# SensorBoard.net
KiCad netlist of a schematic drawn in EAGLE
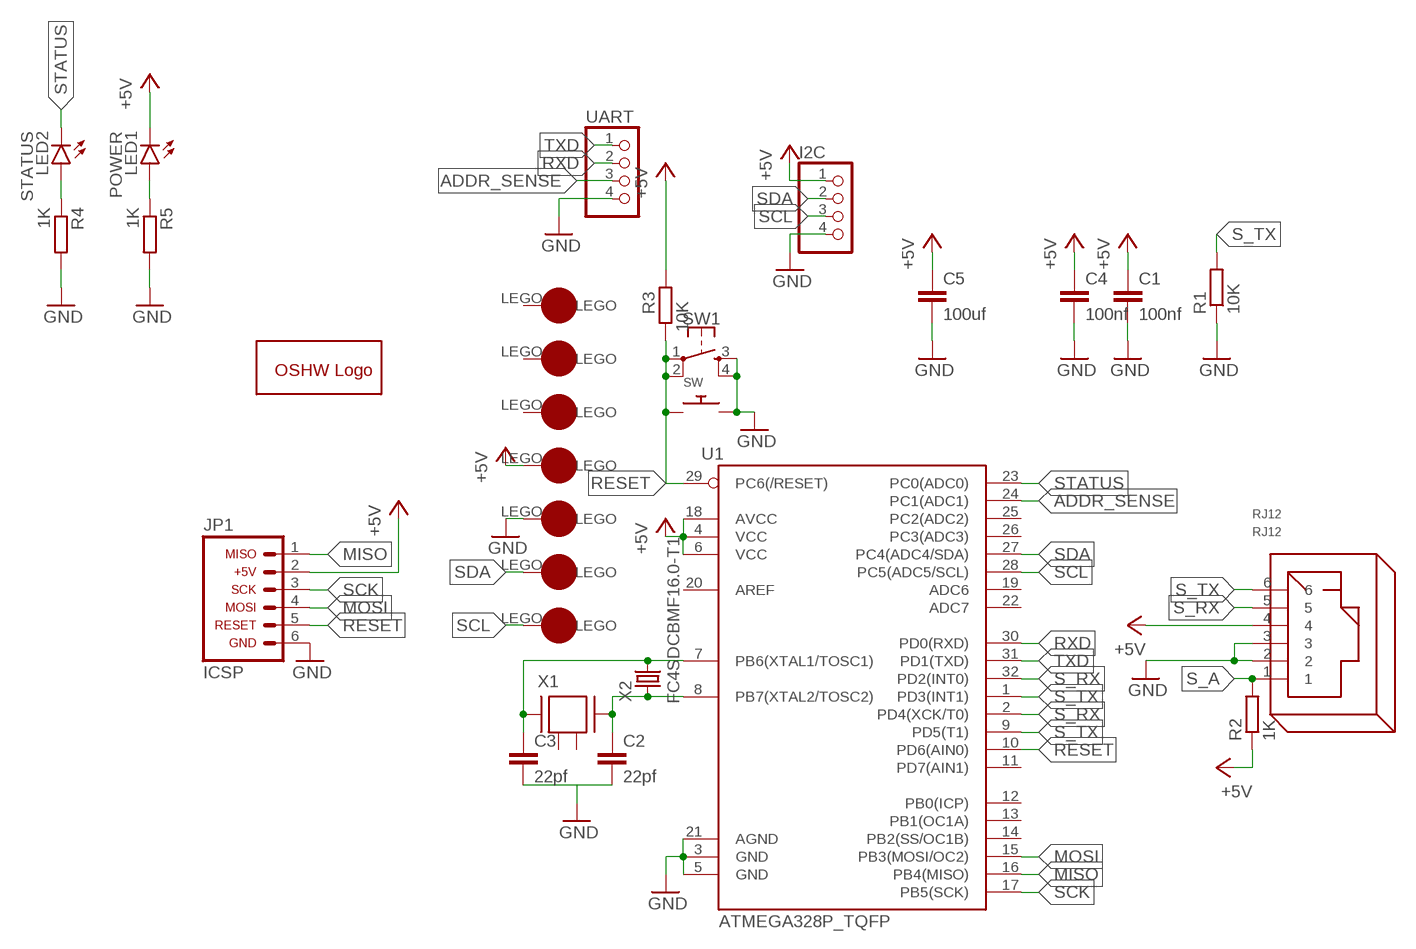
[diagram p0: schematic, sheet 1]

(export (version "E")
  (design (tool "Eeschema 10.0.6"))
  (components
    (comp (ref "C1")
      (value "100nf")
      (footprint "eagle-import:C1206")
      (libsource (lib "eagle-import") (part "C-EUC1206"))
    )
    (comp (ref "C2")
      (value "22pf")
      (footprint "eagle-import:C1206")
      (libsource (lib "eagle-import") (part "C-EUC1206"))
    )
    (comp (ref "C3")
      (value "22pf")
      (footprint "eagle-import:C1206")
      (libsource (lib "eagle-import") (part "C-EUC1206"))
    )
    (comp (ref "C4")
      (value "100nf")
      (footprint "eagle-import:C1206")
      (libsource (lib "eagle-import") (part "C-EUC1206"))
    )
    (comp (ref "C5")
      (value "100uf")
      (footprint "eagle-import:C1206")
      (libsource (lib "eagle-import") (part "C-EUC1206"))
    )
    (comp (ref "I2C")
      (value "PINHD-1X4")
      (footprint "eagle-import:1X04")
      (libsource (lib "eagle-import") (part "PINHD-1X4"))
    )
    (comp (ref "JP1")
      (value "ICSP_HEADER")
      (footprint "eagle-import:ICSP_HEADER")
      (libsource (lib "eagle-import") (part "ICSP_HEADER"))
    )
    (comp (ref "LED1")
      (value "POWER")
      (footprint "eagle-import:1206")
      (libsource (lib "eagle-import") (part "LEDSMT1206"))
    )
    (comp (ref "LED2")
      (value "STATUS")
      (footprint "eagle-import:1206")
      (libsource (lib "eagle-import") (part "LEDSMT1206"))
    )
    (comp (ref "R1")
      (value "10K")
      (footprint "eagle-import:M1206")
      (libsource (lib "eagle-import") (part "R-EU_M1206"))
    )
    (comp (ref "R2")
      (value "1K")
      (footprint "eagle-import:M1206")
      (libsource (lib "eagle-import") (part "R-EU_M1206"))
    )
    (comp (ref "R3")
      (value "10K")
      (footprint "eagle-import:M1206")
      (libsource (lib "eagle-import") (part "R-EU_M1206"))
    )
    (comp (ref "R4")
      (value "1K")
      (footprint "eagle-import:M1206")
      (libsource (lib "eagle-import") (part "R-EU_M1206"))
    )
    (comp (ref "R5")
      (value "1K")
      (footprint "eagle-import:M1206")
      (libsource (lib "eagle-import") (part "R-EU_M1206"))
    )
    (comp (ref "RJ12")
      (value "RJ12")
      (footprint "eagle-import:RJ12")
      (libsource (lib "eagle-import") (part "RJ12"))
    )
    (comp (ref "SW")
      (value "SWITCH_PUSHBUTTONC&K_KSS")
      (footprint "eagle-import:BTN_CK_KSS")
      (libsource (lib "eagle-import") (part "SWITCH_PUSHBUTTONC&K_KSS"))
    )
    (comp (ref "SW1")
      (value "MOMENTARY-SWITCH-SPST-2-SMD-5.2MM")
      (footprint "eagle-import:TACTILE_SWITCH_SMD_5.2MM")
      (libsource (lib "eagle-import") (part "MOMENTARY-SWITCH-SPST-2-SMD-5.2MM"))
    )
    (comp (ref "U$1")
      (value "LEGO-1X1")
      (footprint "eagle-import:LEGO-1X1")
      (libsource (lib "eagle-import") (part "LEGO-1X1"))
    )
    (comp (ref "U$2")
      (value "OPENSOURCE")
      (footprint "eagle-import:OSHW_5MM")
      (libsource (lib "eagle-import") (part "OPENSOURCE"))
    )
    (comp (ref "U$3")
      (value "LEGO-1X1")
      (footprint "eagle-import:LEGO-1X1")
      (libsource (lib "eagle-import") (part "LEGO-1X1"))
    )
    (comp (ref "U$4")
      (value "LEGO-1X1")
      (footprint "eagle-import:LEGO-1X1")
      (libsource (lib "eagle-import") (part "LEGO-1X1"))
    )
    (comp (ref "U$5")
      (value "LEGO-1X1")
      (footprint "eagle-import:LEGO-1X1")
      (libsource (lib "eagle-import") (part "LEGO-1X1"))
    )
    (comp (ref "U$6")
      (value "LEGO-1X1")
      (footprint "eagle-import:LEGO-1X1")
      (libsource (lib "eagle-import") (part "LEGO-1X1"))
    )
    (comp (ref "U$7")
      (value "LEGO-1X1")
      (footprint "eagle-import:LEGO-1X1")
      (libsource (lib "eagle-import") (part "LEGO-1X1"))
    )
    (comp (ref "U$9")
      (value "LEGO-1X1")
      (footprint "eagle-import:LEGO-1X1")
      (libsource (lib "eagle-import") (part "LEGO-1X1"))
    )
    (comp (ref "U1")
      (value "ATMEGA328P_TQFP")
      (footprint "eagle-import:TQFP32-08")
      (libsource (lib "eagle-import") (part "ATMEGA328P_TQFP"))
    )
    (comp (ref "UART")
      (value "PINHD-1X4")
      (footprint "eagle-import:1X04")
      (libsource (lib "eagle-import") (part "PINHD-1X4"))
    )
    (comp (ref "X1")
      (value "7B-16.000MAAJ-T")
      (footprint "eagle-import:7B-16.000MAAJ-T")
      (fields
        (field (name "DIGIKEY_PART_NUMBER") "887-1104-2-ND")
        (field (name "MANUFACTURER") "TXC CORPORATION")
      )
      (libsource (lib "eagle-import") (part "7B-16.000MAAJ-T"))
    )
    (comp (ref "X2")
      (value "FC4SDCBMF16.0-T1")
      (footprint "eagle-import:FC4SDCBMF16.0-T1")
      (fields
        (field (name "DIGIKEY_PART_NUMBER") "631-1017-2-ND")
        (field (name "MANUFACTURER") "Fox Electronics")
        (field (name "CREATED_BY") "PCBLayout.com")
      )
      (libsource (lib "eagle-import") (part "FC4SDCBMF16.0-T1"))
    )
  )
  (nets
    (net (code "1") (name "+5V") (class "Default")
      (node (ref "C1") (pin "1") (pinfunction "1_1") (pintype "passive"))
      (node (ref "C4") (pin "1") (pinfunction "1_1") (pintype "passive"))
      (node (ref "C5") (pin "1") (pinfunction "1_1") (pintype "passive"))
      (node (ref "I2C") (pin "1") (pinfunction "1_1") (pintype "passive"))
      (node (ref "JP1") (pin "2") (pinfunction "2_2") (pintype "passive"))
      (node (ref "LED1") (pin "C") (pinfunction "C_C") (pintype "passive"))
      (node (ref "R2") (pin "1") (pinfunction "1_1") (pintype "passive"))
      (node (ref "R3") (pin "2") (pinfunction "2_2") (pintype "passive"))
      (node (ref "RJ12") (pin "4") (pinfunction "4_4") (pintype "bidirectional"))
      (node (ref "U$5") (pin "LEGO") (pinfunction "LEGO_LEGO") (pintype "bidirectional"))
      (node (ref "U1") (pin "18") (pinfunction "AVCC_18") (pintype "bidirectional"))
      (node (ref "U1") (pin "4") (pinfunction "VCC_4") (pintype "bidirectional"))
      (node (ref "U1") (pin "6") (pinfunction "VCC_6") (pintype "bidirectional"))
    )
    (net (code "2") (name "ADDR_SENSE") (class "Default")
      (node (ref "U1") (pin "24") (pinfunction "PC1(ADC1)_24") (pintype "bidirectional"))
      (node (ref "UART") (pin "3") (pinfunction "3_3") (pintype "passive"))
    )
    (net (code "3") (name "GND") (class "Default")
      (node (ref "C1") (pin "2") (pinfunction "2_2") (pintype "passive"))
      (node (ref "C2") (pin "2") (pinfunction "2_2") (pintype "passive"))
      (node (ref "C3") (pin "2") (pinfunction "2_2") (pintype "passive"))
      (node (ref "C4") (pin "2") (pinfunction "2_2") (pintype "passive"))
      (node (ref "C5") (pin "2") (pinfunction "2_2") (pintype "passive"))
      (node (ref "I2C") (pin "4") (pinfunction "4_4") (pintype "passive"))
      (node (ref "JP1") (pin "6") (pinfunction "6_6") (pintype "passive"))
      (node (ref "R1") (pin "1") (pinfunction "1_1") (pintype "passive"))
      (node (ref "R4") (pin "2") (pinfunction "2_2") (pintype "passive"))
      (node (ref "R5") (pin "2") (pinfunction "2_2") (pintype "passive"))
      (node (ref "RJ12") (pin "2") (pinfunction "2_2") (pintype "bidirectional"))
      (node (ref "RJ12") (pin "3") (pinfunction "3_3") (pintype "bidirectional"))
      (node (ref "SW") (pin "P$2") (pinfunction "P$2_P$2") (pintype "passive"))
      (node (ref "SW1") (pin "3") (pinfunction "3_3") (pintype "passive"))
      (node (ref "SW1") (pin "4") (pinfunction "4_4") (pintype "passive"))
      (node (ref "U$4") (pin "LEGO") (pinfunction "LEGO_LEGO") (pintype "bidirectional"))
      (node (ref "U1") (pin "21") (pinfunction "AGND_21") (pintype "bidirectional"))
      (node (ref "U1") (pin "3") (pinfunction "GND_3") (pintype "bidirectional"))
      (node (ref "U1") (pin "5") (pinfunction "GND_5") (pintype "bidirectional"))
      (node (ref "UART") (pin "4") (pinfunction "4_4") (pintype "passive"))
    )
    (net (code "4") (name "MISO") (class "Default")
      (node (ref "JP1") (pin "1") (pinfunction "1_1") (pintype "passive"))
      (node (ref "U1") (pin "16") (pinfunction "PB4(MISO)_16") (pintype "bidirectional"))
    )
    (net (code "5") (name "MOSI") (class "Default")
      (node (ref "JP1") (pin "4") (pinfunction "4_4") (pintype "passive"))
      (node (ref "U1") (pin "15") (pinfunction "PB3(MOSI/OC2)_15") (pintype "bidirectional"))
    )
    (net (code "6") (name "Net-(LED1-PadA)") (class "Default")
      (node (ref "LED1") (pin "A") (pinfunction "A_A") (pintype "passive"))
      (node (ref "R5") (pin "1") (pinfunction "1_1") (pintype "passive"))
    )
    (net (code "7") (name "Net-(LED2-PadA)") (class "Default")
      (node (ref "LED2") (pin "A") (pinfunction "A_A") (pintype "passive"))
      (node (ref "R4") (pin "1") (pinfunction "1_1") (pintype "passive"))
    )
    (net (code "8") (name "Net-(U1-PB6(XTAL1{slash}TOSC1))") (class "Default")
      (node (ref "C3") (pin "1") (pinfunction "1_1") (pintype "passive"))
      (node (ref "U1") (pin "7") (pinfunction "PB6(XTAL1/TOSC1)_7") (pintype "bidirectional"))
      (node (ref "X1") (pin "1") (pinfunction "1_1") (pintype "passive"))
      (node (ref "X2") (pin "2") (pinfunction "2_2") (pintype "passive"))
    )
    (net (code "9") (name "Net-(U1-PB7(XTAL2{slash}TOSC2))") (class "Default")
      (node (ref "C2") (pin "1") (pinfunction "1_1") (pintype "passive"))
      (node (ref "U1") (pin "8") (pinfunction "PB7(XTAL2/TOSC2)_8") (pintype "bidirectional"))
      (node (ref "X1") (pin "3") (pinfunction "3_3") (pintype "passive"))
      (node (ref "X2") (pin "1") (pinfunction "1_1") (pintype "passive"))
    )
    (net (code "10") (name "RESET") (class "Default")
      (node (ref "JP1") (pin "5") (pinfunction "5_5") (pintype "passive"))
      (node (ref "R3") (pin "1") (pinfunction "1_1") (pintype "passive"))
      (node (ref "SW") (pin "P$1") (pinfunction "P$1_P$1") (pintype "passive"))
      (node (ref "SW1") (pin "1") (pinfunction "1_1") (pintype "passive"))
      (node (ref "SW1") (pin "2") (pinfunction "2_2") (pintype "passive"))
      (node (ref "U1") (pin "10") (pinfunction "PD6(AIN0)_10") (pintype "bidirectional"))
      (node (ref "U1") (pin "29") (pinfunction "PC6(/RESET)_29") (pintype "bidirectional"))
    )
    (net (code "11") (name "RXD") (class "Default")
      (node (ref "U1") (pin "30") (pinfunction "PD0(RXD)_30") (pintype "bidirectional"))
      (node (ref "UART") (pin "2") (pinfunction "2_2") (pintype "passive"))
    )
    (net (code "12") (name "SCK") (class "Default")
      (node (ref "JP1") (pin "3") (pinfunction "3_3") (pintype "passive"))
      (node (ref "U1") (pin "17") (pinfunction "PB5(SCK)_17") (pintype "bidirectional"))
    )
    (net (code "13") (name "SCL") (class "Default")
      (node (ref "I2C") (pin "3") (pinfunction "3_3") (pintype "passive"))
      (node (ref "U$1") (pin "LEGO") (pinfunction "LEGO_LEGO") (pintype "bidirectional"))
      (node (ref "U1") (pin "28") (pinfunction "PC5(ADC5/SCL)_28") (pintype "bidirectional"))
    )
    (net (code "14") (name "SDA") (class "Default")
      (node (ref "I2C") (pin "2") (pinfunction "2_2") (pintype "passive"))
      (node (ref "U$3") (pin "LEGO") (pinfunction "LEGO_LEGO") (pintype "bidirectional"))
      (node (ref "U1") (pin "27") (pinfunction "PC4(ADC4/SDA)_27") (pintype "bidirectional"))
    )
    (net (code "15") (name "STATUS") (class "Default")
      (node (ref "LED2") (pin "C") (pinfunction "C_C") (pintype "passive"))
      (node (ref "U1") (pin "23") (pinfunction "PC0(ADC0)_23") (pintype "bidirectional"))
    )
    (net (code "16") (name "S_A") (class "Default")
      (node (ref "R2") (pin "2") (pinfunction "2_2") (pintype "passive"))
      (node (ref "RJ12") (pin "1") (pinfunction "1_1") (pintype "bidirectional"))
    )
    (net (code "17") (name "S_RX") (class "Default")
      (node (ref "RJ12") (pin "5") (pinfunction "5_5") (pintype "bidirectional"))
      (node (ref "U1") (pin "2") (pinfunction "PD4(XCK/T0)_2") (pintype "bidirectional"))
      (node (ref "U1") (pin "32") (pinfunction "PD2(INT0)_32") (pintype "bidirectional"))
    )
    (net (code "18") (name "S_TX") (class "Default")
      (node (ref "R1") (pin "2") (pinfunction "2_2") (pintype "passive"))
      (node (ref "RJ12") (pin "6") (pinfunction "6_6") (pintype "bidirectional"))
      (node (ref "U1") (pin "1") (pinfunction "PD3(INT1)_1") (pintype "bidirectional"))
      (node (ref "U1") (pin "9") (pinfunction "PD5(T1)_9") (pintype "bidirectional"))
    )
    (net (code "19") (name "TXD") (class "Default")
      (node (ref "U1") (pin "31") (pinfunction "PD1(TXD)_31") (pintype "bidirectional"))
      (node (ref "UART") (pin "1") (pinfunction "1_1") (pintype "passive"))
    )
    (net (code "20") (name "unconnected-(U$6-PadLEGO)") (class "Default")
      (node (ref "U$6") (pin "LEGO") (pinfunction "LEGO_LEGO") (pintype "bidirectional"))
    )
    (net (code "21") (name "unconnected-(U$7-PadLEGO)") (class "Default")
      (node (ref "U$7") (pin "LEGO") (pinfunction "LEGO_LEGO") (pintype "bidirectional"))
    )
    (net (code "22") (name "unconnected-(U$9-PadLEGO)") (class "Default")
      (node (ref "U$9") (pin "LEGO") (pinfunction "LEGO_LEGO") (pintype "bidirectional"))
    )
    (net (code "23") (name "unconnected-(U1-ADC6-Pad19)") (class "Default")
      (node (ref "U1") (pin "19") (pinfunction "ADC6_19") (pintype "bidirectional"))
    )
    (net (code "24") (name "unconnected-(U1-ADC7-Pad22)") (class "Default")
      (node (ref "U1") (pin "22") (pinfunction "ADC7_22") (pintype "bidirectional"))
    )
    (net (code "25") (name "unconnected-(U1-AREF-Pad20)") (class "Default")
      (node (ref "U1") (pin "20") (pinfunction "AREF_20") (pintype "bidirectional"))
    )
    (net (code "26") (name "unconnected-(U1-PB0(ICP)-Pad12)") (class "Default")
      (node (ref "U1") (pin "12") (pinfunction "PB0(ICP)_12") (pintype "bidirectional"))
    )
    (net (code "27") (name "unconnected-(U1-PB1(OC1A)-Pad13)") (class "Default")
      (node (ref "U1") (pin "13") (pinfunction "PB1(OC1A)_13") (pintype "bidirectional"))
    )
    (net (code "28") (name "unconnected-(U1-PB2(SS{slash}OC1B)-Pad14)") (class "Default")
      (node (ref "U1") (pin "14") (pinfunction "PB2(SS/OC1B)_14") (pintype "bidirectional"))
    )
    (net (code "29") (name "unconnected-(U1-PC2(ADC2)-Pad25)") (class "Default")
      (node (ref "U1") (pin "25") (pinfunction "PC2(ADC2)_25") (pintype "bidirectional"))
    )
    (net (code "30") (name "unconnected-(U1-PC3(ADC3)-Pad26)") (class "Default")
      (node (ref "U1") (pin "26") (pinfunction "PC3(ADC3)_26") (pintype "bidirectional"))
    )
    (net (code "31") (name "unconnected-(U1-PD7(AIN1)-Pad11)") (class "Default")
      (node (ref "U1") (pin "11") (pinfunction "PD7(AIN1)_11") (pintype "bidirectional"))
    )
    (net (code "32") (name "unconnected-(X1-Pad2)") (class "Default")
      (node (ref "X1") (pin "2") (pinfunction "2_2") (pintype "passive"))
    )
    (net (code "33") (name "unconnected-(X1-Pad4)") (class "Default")
      (node (ref "X1") (pin "4") (pinfunction "4_4") (pintype "passive"))
    )
  )
)
